# CarteAction2026.net
KiCad netlist of a schematic drawn in Altium Designer
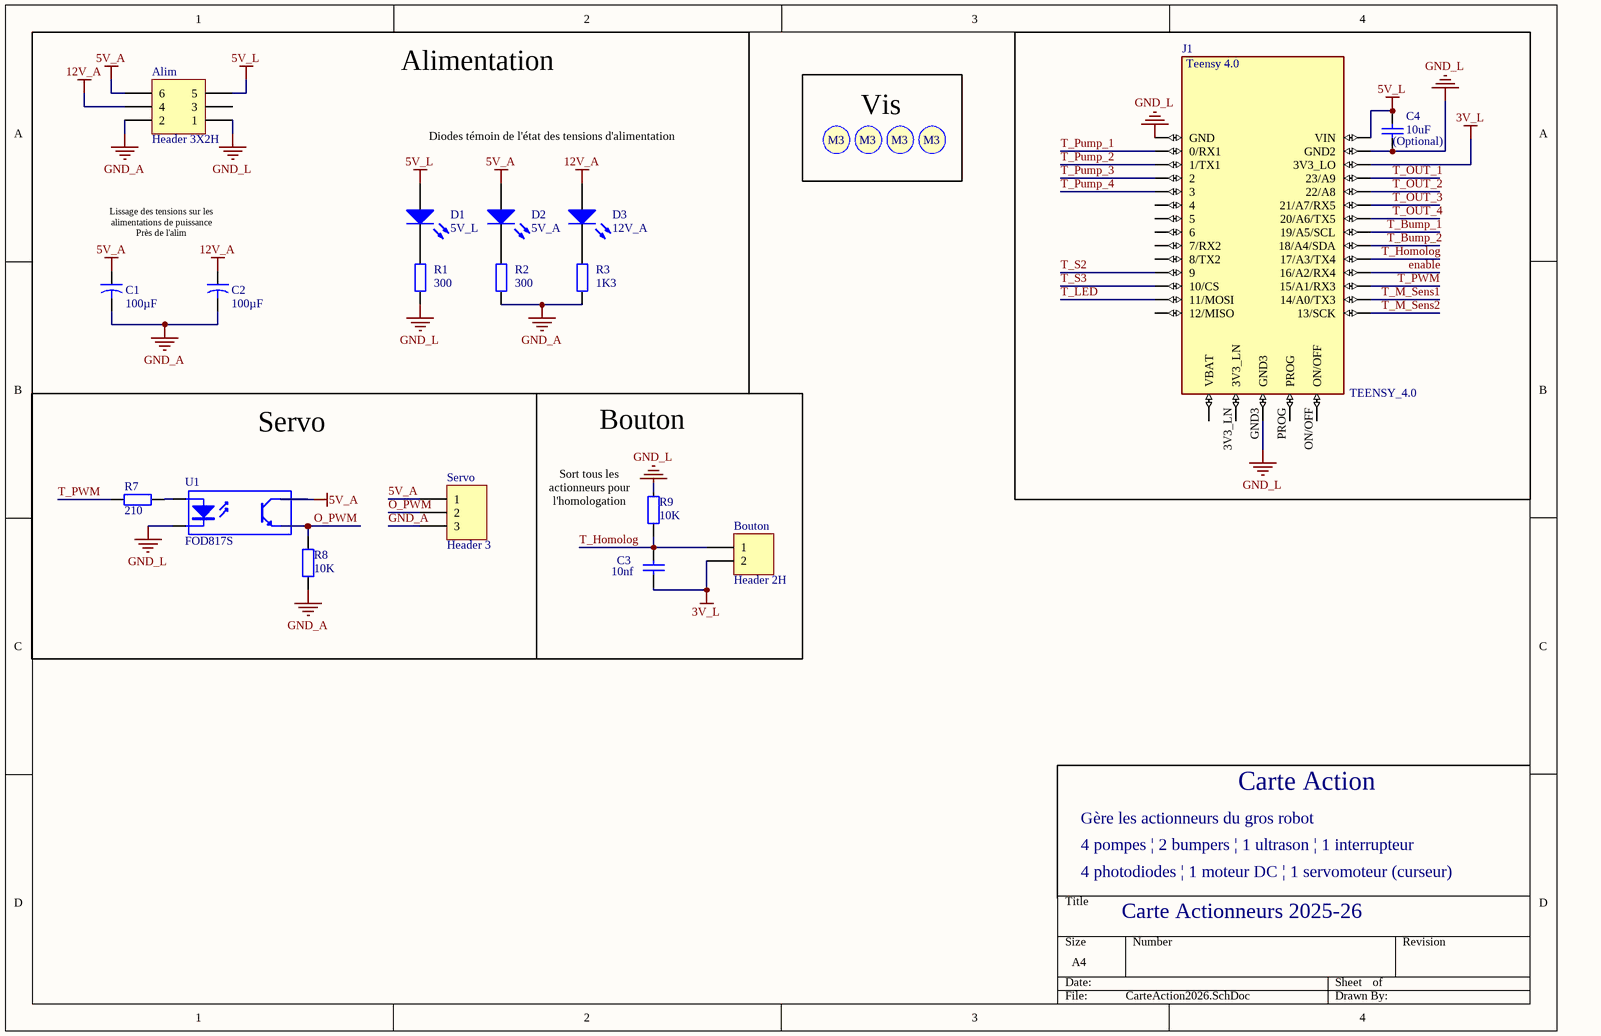
[diagram p0: CarteAction2026.SchDoc]

(export (version "E")
  (design (tool "Eeschema 10.0.6"))
  (components
    (comp (ref "Alim")
      (value "Header 3X2H")
      (footprint "MOLEX_MINIFITJR_3X2")
      (description "Header, 3-Pin, Dual row, Right Angle")
      (fields (field (name "PUBLISHER") "Altium Limited"))
      (libsource (lib "Miscellaneous Connectors") (part "Header 3X2H"))
    )
    (comp (ref "Bouton")
      (value "Header 2H")
      (footprint "S2B-XH-A")
      (description "Header, 2-Pin, Right Angle")
      (fields (field (name "PUBLISHER") "Altium Limited"))
      (libsource (lib "Miscellaneous Connectors") (part "Header 2H"))
    )
    (comp (ref "C1")
      (value "100µF")
      (footprint "Condensateur")
      (description "Capacitor")
      (fields (field (name "Comment") "Cap2") (field (name "PUBLISHER") "Altium Limited"))
      (libsource (lib "Miscellaneous Devices") (part "Cap2"))
    )
    (comp (ref "C2")
      (value "100µF")
      (footprint "Condensateur")
      (description "Capacitor")
      (fields (field (name "Comment") "Cap2") (field (name "PUBLISHER") "Altium Limited"))
      (libsource (lib "Miscellaneous Devices") (part "Cap2"))
    )
    (comp (ref "C3")
      (value "10nf")
      (footprint "Capacitor 1206")
      (description "Capacitor")
      (fields (field (name "Comment") "Cap") (field (name "PUBLISHER") "Altium Limited"))
      (libsource (lib "Miscellaneous Devices") (part "Cap"))
    )
    (comp (ref "C4")
      (value "(Optional)")
      (footprint "Capacitor 1206")
      (description "Capacitor")
      (fields (field (name "ALTIUM_VALUE") "10uF") (field (name "PUBLISHER") "Altium Limited"))
      (libsource (lib "Miscellaneous Devices") (part "Cap"))
    )
    (comp (ref "D1")
      (value "5V_L")
      (footprint "KP-3216SEC")
      (description "Typical RED, GREEN, YELLOW, AMBER GaAs LED")
      (fields (field (name "PUBLISHER") "Altium Limited"))
      (libsource (lib "Miscellaneous Devices") (part "LED2"))
    )
    (comp (ref "D2")
      (value "5V_A")
      (footprint "KP-3216SEC")
      (description "Typical RED, GREEN, YELLOW, AMBER GaAs LED")
      (fields (field (name "PUBLISHER") "Altium Limited"))
      (libsource (lib "Miscellaneous Devices") (part "LED2"))
    )
    (comp (ref "D3")
      (value "12V_A")
      (footprint "KP-3216SEC")
      (description "Typical RED, GREEN, YELLOW, AMBER GaAs LED")
      (fields (field (name "PUBLISHER") "Altium Limited"))
      (libsource (lib "Miscellaneous Devices") (part "LED2"))
    )
    (comp (ref "J1")
      (value "TEENSY_4.0")
      (footprint "TEENSY_4.0")
      (fields (field (name "MF") "PJRC") (field (name "MP") "Teensy 4.0"))
      (libsource (lib "TEENSY_4.0") (part "TEENSY_4.0"))
    )
    (comp (ref "R1")
      (value "300")
      (footprint "Resistor 1206")
      (description "Resistor")
      (fields (field (name "Comment") "Res2") (field (name "PUBLISHER") "Altium Limited"))
      (libsource (lib "") (part "Res2_1"))
    )
    (comp (ref "R2")
      (value "300")
      (footprint "Resistor 1206")
      (description "Resistor")
      (fields (field (name "Comment") "Res2") (field (name "PUBLISHER") "Altium Limited"))
      (libsource (lib "Miscellaneous Devices") (part "Res2"))
    )
    (comp (ref "R3")
      (value "1K3")
      (footprint "Resistor 1206")
      (description "Resistor")
      (fields (field (name "Comment") "Res2") (field (name "PUBLISHER") "Altium Limited"))
      (libsource (lib "Miscellaneous Devices") (part "Res2"))
    )
    (comp (ref "R7")
      (value "210")
      (footprint "Resistor 1206")
      (description "Resistor")
      (fields (field (name "PUBLISHER") "Altium Limited"))
      (libsource (lib "") (part "Res2_2"))
    )
    (comp (ref "R8")
      (value "10K")
      (footprint "Resistor 1206")
      (description "Resistor")
      (fields (field (name "Comment") "Res2") (field (name "PUBLISHER") "Altium Limited"))
      (libsource (lib "") (part "Res2_1"))
    )
    (comp (ref "R9")
      (value "10K")
      (footprint "Resistor 1206")
      (description "Resistor")
      (fields (field (name "Comment") "Res2") (field (name "PUBLISHER") "Altium Limited"))
      (libsource (lib "Miscellaneous Devices") (part "Res2"))
    )
    (comp (ref "S1")
      (value "Screw M3")
      (footprint "Screw M3")
      (libsource (lib "Robot_2019") (part "Screw M3"))
    )
    (comp (ref "S2")
      (value "Screw M3")
      (footprint "Screw M3")
      (libsource (lib "Robot_2019") (part "Screw M3"))
    )
    (comp (ref "S3")
      (value "Screw M3")
      (footprint "Screw M3")
      (libsource (lib "Robot_2019") (part "Screw M3"))
    )
    (comp (ref "S4")
      (value "Screw M3")
      (footprint "Screw M3")
      (libsource (lib "Robot_2019") (part "Screw M3"))
    )
    (comp (ref "Servo")
      (value "Header 3")
      (footprint "S3B-XH-A")
      (description "Header, 3-Pin")
      (fields (field (name "PUBLISHER") "Altium Limited"))
      (libsource (lib "Miscellaneous Connectors") (part "Header 3"))
    )
    (comp (ref "U1")
      (value "FOD817S")
      (footprint "SOP254P1016X385-4N")
      (description "4-Pin Phototransistor Optocoupler")
      (fields (field (name "PUBLISHER") "Altium Limited"))
      (libsource (lib "Miscellaneous Devices") (part "Optoisolator1"))
    )
  )
  (nets
    (net (code "1") (name "/O_PWM") (class "Default")
      (node (ref "R8") (pin "2") (pinfunction "2_2") (pintype "passive"))
      (node (ref "Servo") (pin "2") (pinfunction "2_2") (pintype "passive"))
      (node (ref "U1") (pin "3") (pinfunction "E_3") (pintype "passive"))
    )
    (net (code "2") (name "/T_Bump_1") (class "Default")
      (node (ref "J1") (pin "19/A5/SCL") (pinfunction "19/A5/SCL_19/A5/SCL") (pintype "bidirectional"))
    )
    (net (code "3") (name "/T_Bump_2") (class "Default")
      (node (ref "J1") (pin "18/A4/SDA") (pinfunction "18/A4/SDA_18/A4/SDA") (pintype "bidirectional"))
    )
    (net (code "4") (name "/T_Homolog") (class "Default")
      (node (ref "Bouton") (pin "1") (pinfunction "1_1") (pintype "passive"))
      (node (ref "C3") (pin "2") (pinfunction "2_2") (pintype "passive"))
      (node (ref "J1") (pin "17/A3") (pinfunction "17/A3/TX4_17/A3") (pintype "bidirectional"))
      (node (ref "R9") (pin "2") (pinfunction "2_2") (pintype "passive"))
    )
    (net (code "5") (name "/T_LED") (class "Default")
      (node (ref "J1") (pin "11/MOSI") (pinfunction "11/MOSI_11/MOSI") (pintype "bidirectional"))
    )
    (net (code "6") (name "/T_M_Sens1") (class "Default")
      (node (ref "J1") (pin "14/A0") (pinfunction "14/A0/TX3_14/A0") (pintype "bidirectional"))
    )
    (net (code "7") (name "/T_M_Sens2") (class "Default")
      (node (ref "J1") (pin "13/SCK") (pinfunction "13/SCK_13/SCK") (pintype "bidirectional"))
    )
    (net (code "8") (name "/T_OUT_1") (class "Default")
      (node (ref "J1") (pin "23/A9") (pinfunction "23/A9_23/A9") (pintype "bidirectional"))
    )
    (net (code "9") (name "/T_OUT_2") (class "Default")
      (node (ref "J1") (pin "22/A8") (pinfunction "22/A8_22/A8") (pintype "bidirectional"))
    )
    (net (code "10") (name "/T_OUT_3") (class "Default")
      (node (ref "J1") (pin "21/A7") (pinfunction "21/A7/RX5_21/A7") (pintype "bidirectional"))
    )
    (net (code "11") (name "/T_OUT_4") (class "Default")
      (node (ref "J1") (pin "20/A6") (pinfunction "20/A6/TX5_20/A6") (pintype "bidirectional"))
    )
    (net (code "12") (name "/T_PWM") (class "Default")
      (node (ref "J1") (pin "15/A1") (pinfunction "15/A1/RX3_15/A1") (pintype "bidirectional"))
      (node (ref "R7") (pin "1") (pinfunction "1_1") (pintype "passive"))
    )
    (net (code "13") (name "/T_Pump_1") (class "Default")
      (node (ref "J1") (pin "0/RX") (pinfunction "0/RX1_0/RX") (pintype "bidirectional"))
    )
    (net (code "14") (name "/T_Pump_2") (class "Default")
      (node (ref "J1") (pin "1/TX") (pinfunction "1/TX1_1/TX") (pintype "bidirectional"))
    )
    (net (code "15") (name "/T_Pump_3") (class "Default")
      (node (ref "J1") (pin "2") (pinfunction "2_2") (pintype "bidirectional"))
    )
    (net (code "16") (name "/T_Pump_4") (class "Default")
      (node (ref "J1") (pin "3/CANTX") (pinfunction "3_3/CANTX") (pintype "bidirectional"))
    )
    (net (code "17") (name "/T_S2") (class "Default")
      (node (ref "J1") (pin "9/CS") (pinfunction "9_9/CS") (pintype "bidirectional"))
    )
    (net (code "18") (name "/T_S3") (class "Default")
      (node (ref "J1") (pin "10/CS") (pinfunction "10/CS_10/CS") (pintype "bidirectional"))
    )
    (net (code "19") (name "/enable") (class "Default")
      (node (ref "J1") (pin "16/A2") (pinfunction "16/A2/RX4_16/A2") (pintype "bidirectional"))
    )
    (net (code "20") (name "3V_L") (class "Default")
      (node (ref "Bouton") (pin "2") (pinfunction "2_2") (pintype "passive"))
      (node (ref "C3") (pin "1") (pinfunction "1_1") (pintype "passive"))
      (node (ref "J1") (pin "3V3_LO") (pinfunction "3V3_LO_3V3_LO") (pintype "bidirectional"))
    )
    (net (code "21") (name "5V_A") (class "Default")
      (node (ref "Alim") (pin "6") (pinfunction "6_6") (pintype "passive"))
      (node (ref "C1") (pin "1") (pinfunction "1_1") (pintype "passive"))
      (node (ref "D2") (pin "1") (pinfunction "A_1") (pintype "passive"))
      (node (ref "Servo") (pin "1") (pinfunction "1_1") (pintype "passive"))
      (node (ref "U1") (pin "4") (pinfunction "C_4") (pintype "passive"))
    )
    (net (code "22") (name "5V_L") (class "Default")
      (node (ref "Alim") (pin "5") (pinfunction "5_5") (pintype "passive"))
      (node (ref "C4") (pin "2") (pinfunction "2_2") (pintype "passive"))
      (node (ref "D1") (pin "1") (pinfunction "A_1") (pintype "passive"))
      (node (ref "J1") (pin "VIN") (pinfunction "VIN_VIN") (pintype "bidirectional"))
    )
    (net (code "23") (name "12V_A") (class "Default")
      (node (ref "Alim") (pin "4") (pinfunction "4_4") (pintype "passive"))
      (node (ref "C2") (pin "1") (pinfunction "1_1") (pintype "passive"))
      (node (ref "D3") (pin "1") (pinfunction "A_1") (pintype "passive"))
    )
    (net (code "24") (name "GND_A") (class "Default")
      (node (ref "Alim") (pin "2") (pinfunction "2_2") (pintype "passive"))
      (node (ref "C1") (pin "2") (pinfunction "2_2") (pintype "passive"))
      (node (ref "C2") (pin "2") (pinfunction "2_2") (pintype "passive"))
      (node (ref "R2") (pin "2") (pinfunction "2_2") (pintype "passive"))
      (node (ref "R3") (pin "2") (pinfunction "2_2") (pintype "passive"))
      (node (ref "R8") (pin "1") (pinfunction "1_1") (pintype "passive"))
      (node (ref "Servo") (pin "3") (pinfunction "3_3") (pintype "passive"))
    )
    (net (code "25") (name "GND_L") (class "Default")
      (node (ref "Alim") (pin "1") (pinfunction "1_1") (pintype "passive"))
      (node (ref "C4") (pin "1") (pinfunction "1_1") (pintype "passive"))
      (node (ref "J1") (pin "GND") (pinfunction "GND_GND") (pintype "bidirectional"))
      (node (ref "J1") (pin "GND2") (pinfunction "GND2_GND2") (pintype "bidirectional"))
      (node (ref "J1") (pin "GND3") (pinfunction "GND3_GND3") (pintype "bidirectional"))
      (node (ref "R1") (pin "1") (pinfunction "1_1") (pintype "passive"))
      (node (ref "R9") (pin "1") (pinfunction "1_1") (pintype "passive"))
      (node (ref "U1") (pin "2") (pinfunction "K_2") (pintype "passive"))
    )
    (net (code "26") (name "Net-(D1-K)") (class "Default")
      (node (ref "D1") (pin "2") (pinfunction "K_2") (pintype "passive"))
      (node (ref "R1") (pin "2") (pinfunction "2_2") (pintype "passive"))
    )
    (net (code "27") (name "Net-(D2-K)") (class "Default")
      (node (ref "D2") (pin "2") (pinfunction "K_2") (pintype "passive"))
      (node (ref "R2") (pin "1") (pinfunction "1_1") (pintype "passive"))
    )
    (net (code "28") (name "Net-(D3-K)") (class "Default")
      (node (ref "D3") (pin "2") (pinfunction "K_2") (pintype "passive"))
      (node (ref "R3") (pin "1") (pinfunction "1_1") (pintype "passive"))
    )
    (net (code "29") (name "Net-(U1-A)") (class "Default")
      (node (ref "R7") (pin "2") (pinfunction "2_2") (pintype "passive"))
      (node (ref "U1") (pin "1") (pinfunction "A_1") (pintype "passive"))
    )
    (net (code "30") (name "unconnected-(Alim-Pad3)") (class "Default")
      (node (ref "Alim") (pin "3") (pinfunction "3_3") (pintype "passive"))
    )
    (net (code "31") (name "unconnected-(J1-4-Pad4{slash}CANRX)") (class "Default")
      (node (ref "J1") (pin "4/CANRX") (pinfunction "4_4/CANRX") (pintype "bidirectional"))
    )
    (net (code "32") (name "unconnected-(J1-7{slash}RX2-Pad7)") (class "Default")
      (node (ref "J1") (pin "7") (pinfunction "7/RX2_7") (pintype "bidirectional"))
    )
    (net (code "33") (name "unconnected-(J1-8{slash}TX2-Pad8)") (class "Default")
      (node (ref "J1") (pin "8") (pinfunction "8/TX2_8") (pintype "bidirectional"))
    )
    (net (code "34") (name "unconnected-(J1-Pad3V3_LN)") (class "Default")
      (node (ref "J1") (pin "3V3_LN") (pinfunction "3V3_LN_3V3_LN") (pintype "bidirectional"))
    )
    (net (code "35") (name "unconnected-(J1-Pad5)") (class "Default")
      (node (ref "J1") (pin "5") (pinfunction "5_5") (pintype "bidirectional"))
    )
    (net (code "36") (name "unconnected-(J1-Pad6)") (class "Default")
      (node (ref "J1") (pin "6") (pinfunction "6_6") (pintype "bidirectional"))
    )
    (net (code "37") (name "unconnected-(J1-Pad12{slash}MISO)") (class "Default")
      (node (ref "J1") (pin "12/MISO") (pinfunction "12/MISO_12/MISO") (pintype "bidirectional"))
    )
    (net (code "38") (name "unconnected-(J1-PadON{slash}OFF)") (class "Default")
      (node (ref "J1") (pin "ON/OFF") (pinfunction "ON/OFF_ON/OFF") (pintype "bidirectional"))
    )
    (net (code "39") (name "unconnected-(J1-PadPROG)") (class "Default")
      (node (ref "J1") (pin "PROG") (pinfunction "PROG_PROG") (pintype "bidirectional"))
    )
    (net (code "40") (name "unconnected-(J1-VBAT-PadVBA~{T})") (class "Default")
      (node (ref "J1") (pin "VBA~{T}") (pinfunction "VBAT_VBA~{T}") (pintype "bidirectional"))
    )
  )
)
